# Yay_n_Ders_3.net
KiCad netlist of a schematic drawn in EAGLE
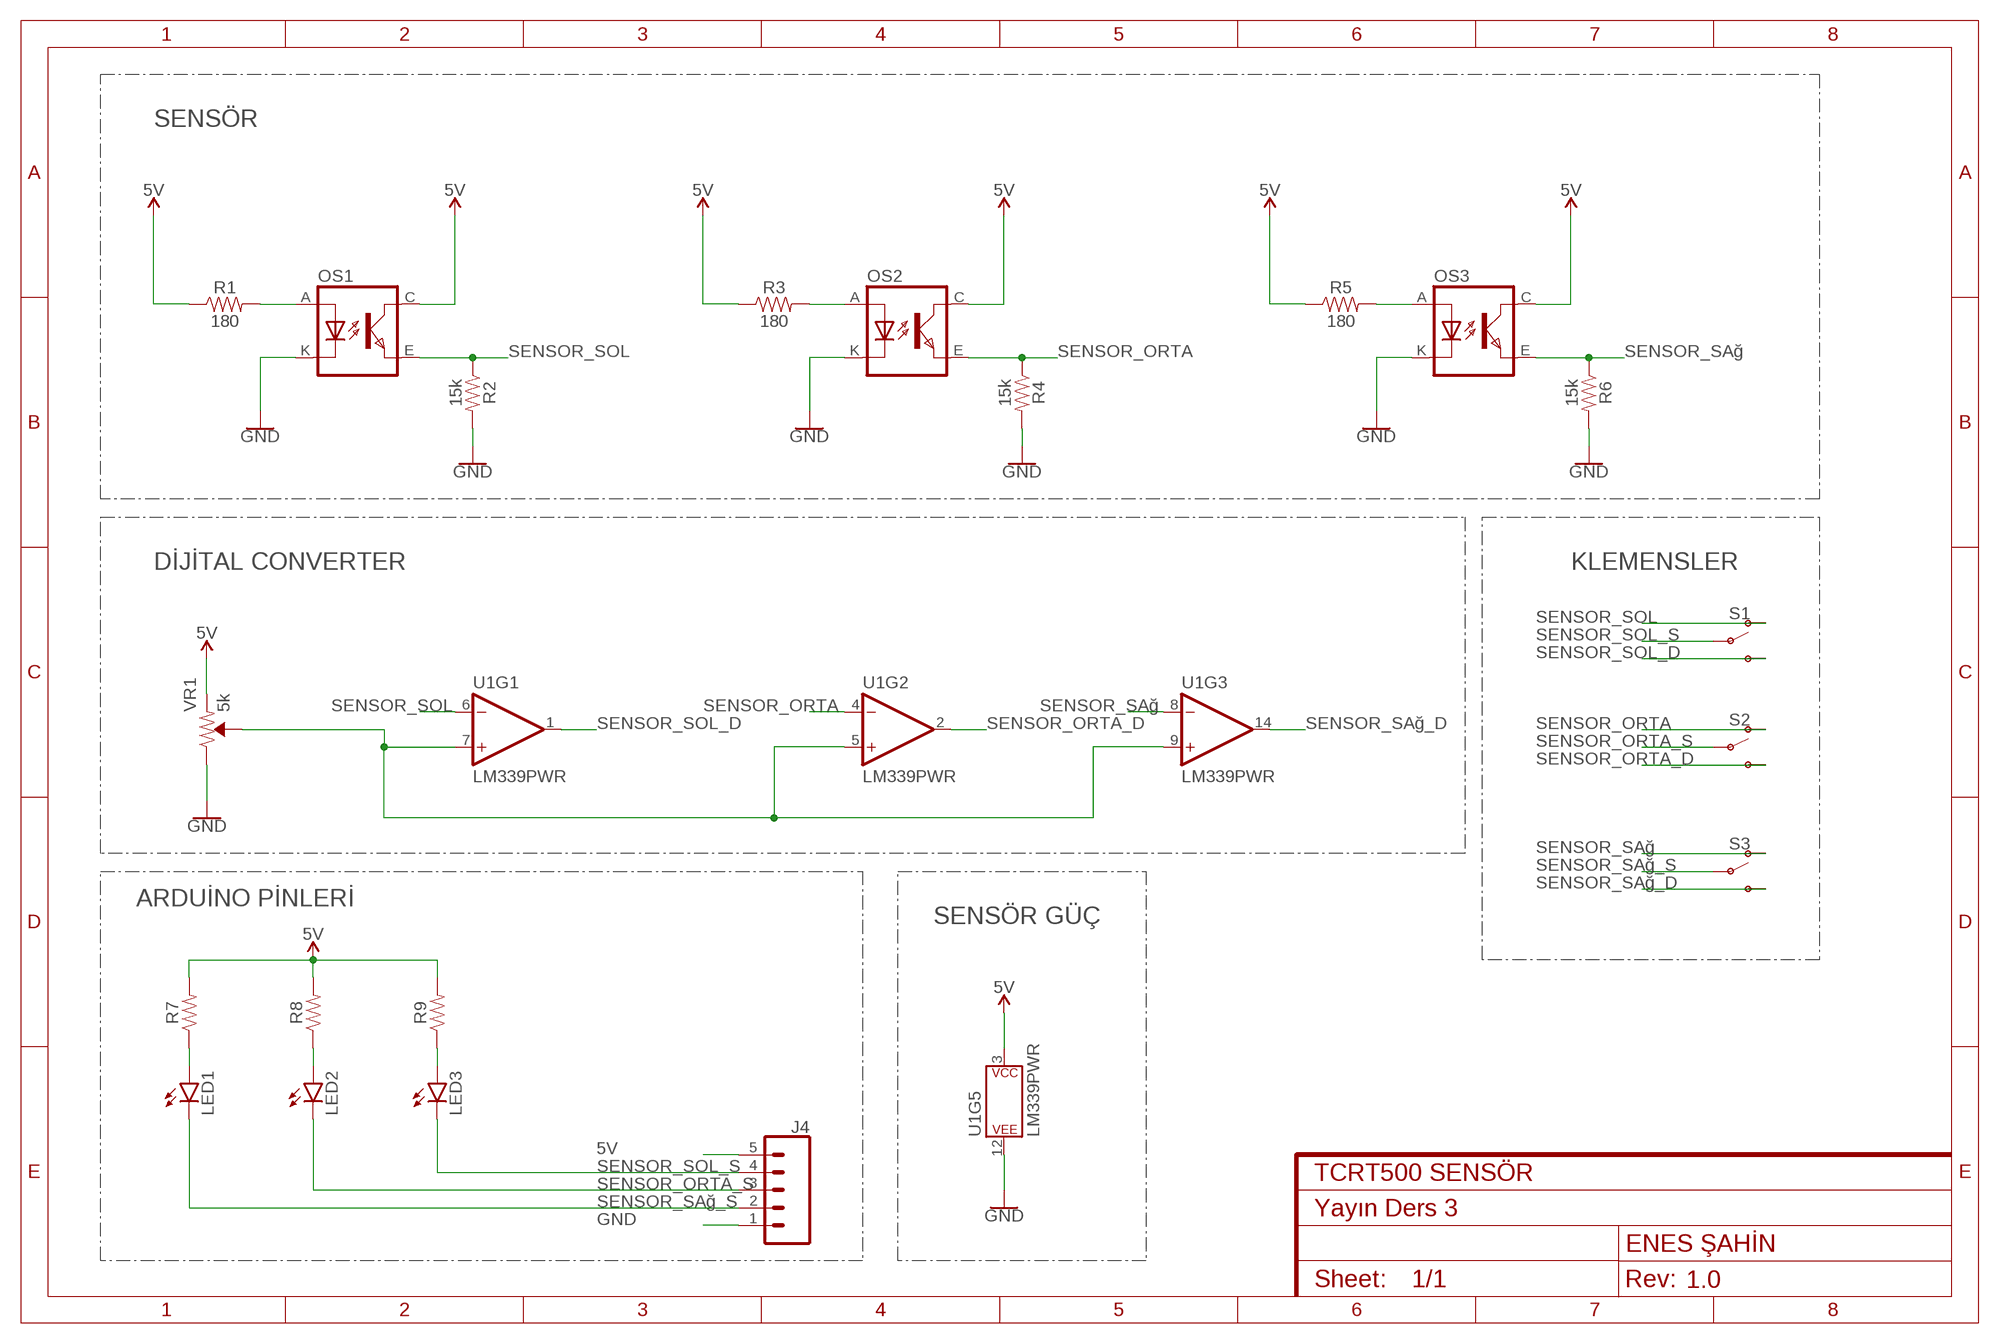
[diagram p0: schematic, sheet 1]

(export (version "E")
  (design (tool "Eeschema 10.0.6"))
  (components
    (comp (ref "J4")
      (value "CONN_05")
      (footprint "eagle-import:1X05")
      (libsource (lib "eagle-import") (part "CONN_05"))
    )
    (comp (ref "LED1")
      (value "LEDCHIP-LED0805")
      (footprint "eagle-import:CHIP-LED0805")
      (libsource (lib "eagle-import") (part "LEDCHIP-LED0805"))
    )
    (comp (ref "LED2")
      (value "LEDCHIP-LED0805")
      (footprint "eagle-import:CHIP-LED0805")
      (libsource (lib "eagle-import") (part "LEDCHIP-LED0805"))
    )
    (comp (ref "LED3")
      (value "LEDCHIP-LED0805")
      (footprint "eagle-import:CHIP-LED0805")
      (libsource (lib "eagle-import") (part "LEDCHIP-LED0805"))
    )
    (comp (ref "OS1")
      (value "TCRT5000")
      (footprint "eagle-import:TCRT5000")
      (libsource (lib "eagle-import") (part "TCRT5000"))
    )
    (comp (ref "OS2")
      (value "TCRT5000")
      (footprint "eagle-import:TCRT5000")
      (libsource (lib "eagle-import") (part "TCRT5000"))
    )
    (comp (ref "OS3")
      (value "TCRT5000")
      (footprint "eagle-import:TCRT5000")
      (libsource (lib "eagle-import") (part "TCRT5000"))
    )
    (comp (ref "R1")
      (value "180")
      (footprint "eagle-import:0805")
      (libsource (lib "eagle-import") (part "0.75OHM-0805-1/4W-1%"))
    )
    (comp (ref "R2")
      (value "15k")
      (footprint "eagle-import:0805")
      (libsource (lib "eagle-import") (part "0.75OHM-0805-1/4W-1%"))
    )
    (comp (ref "R3")
      (value "180")
      (footprint "eagle-import:0805")
      (libsource (lib "eagle-import") (part "0.75OHM-0805-1/4W-1%"))
    )
    (comp (ref "R4")
      (value "15k")
      (footprint "eagle-import:0805")
      (libsource (lib "eagle-import") (part "0.75OHM-0805-1/4W-1%"))
    )
    (comp (ref "R5")
      (value "180")
      (footprint "eagle-import:0805")
      (libsource (lib "eagle-import") (part "0.75OHM-0805-1/4W-1%"))
    )
    (comp (ref "R6")
      (value "15k")
      (footprint "eagle-import:0805")
      (libsource (lib "eagle-import") (part "0.75OHM-0805-1/4W-1%"))
    )
    (comp (ref "R7")
      (value "RESISTOR0805")
      (footprint "eagle-import:0805")
      (libsource (lib "eagle-import") (part "RESISTOR0805"))
    )
    (comp (ref "R8")
      (value "RESISTOR0805")
      (footprint "eagle-import:0805")
      (libsource (lib "eagle-import") (part "RESISTOR0805"))
    )
    (comp (ref "R9")
      (value "RESISTOR0805")
      (footprint "eagle-import:0805")
      (libsource (lib "eagle-import") (part "RESISTOR0805"))
    )
    (comp (ref "S1")
      (value "SWITCH-SPDT-SMD-RIGHT-ANGLE")
      (footprint "eagle-import:SWITCH_SPST_SMD_A")
      (libsource (lib "eagle-import") (part "SWITCH-SPDT-SMD-RIGHT-ANGLE"))
    )
    (comp (ref "S2")
      (value "SWITCH-SPDT-SMD-RIGHT-ANGLE")
      (footprint "eagle-import:SWITCH_SPST_SMD_A")
      (libsource (lib "eagle-import") (part "SWITCH-SPDT-SMD-RIGHT-ANGLE"))
    )
    (comp (ref "S3")
      (value "SWITCH-SPDT-SMD-RIGHT-ANGLE")
      (footprint "eagle-import:SWITCH_SPST_SMD_A")
      (libsource (lib "eagle-import") (part "SWITCH-SPDT-SMD-RIGHT-ANGLE"))
    )
    (comp (ref "U1")
      (value "LM339PWR")
      (footprint "eagle-import:TSSOP-14")
      (libsource (lib "eagle-import") (part "LM339"))
    )
    (comp (ref "VR1")
      (value "5k")
      (footprint "eagle-import:TRIMPOT-SMD-5MM")
      (libsource (lib "eagle-import") (part "TRIMPOT-SMD-5MM-CLOSED-1/4W-20%"))
    )
  )
  (nets
    (net (code "1") (name "/SENSOR_ORTA") (class "Default")
      (node (ref "OS2") (pin "E") (pinfunction "EMITTER_E") (pintype "passive"))
      (node (ref "R4") (pin "1") (pinfunction "1_1") (pintype "passive"))
      (node (ref "S2") (pin "1") (pinfunction "O_1") (pintype "passive"))
      (node (ref "U1") (pin "4") (pinfunction "-IN_4") (pintype "input"))
    )
    (net (code "2") (name "/SENSOR_ORTA_D") (class "Default")
      (node (ref "S2") (pin "3") (pinfunction "S_3") (pintype "passive"))
      (node (ref "U1") (pin "2") (pinfunction "OUT_2") (pintype "output"))
    )
    (net (code "3") (name "/SENSOR_ORTA_S") (class "Default")
      (node (ref "J4") (pin "3") (pinfunction "3_3") (pintype "passive"))
      (node (ref "LED2") (pin "C") (pinfunction "C_C") (pintype "passive"))
      (node (ref "S2") (pin "2") (pinfunction "P_2") (pintype "passive"))
    )
    (net (code "4") (name "/SENSOR_SAğ") (class "Default")
      (node (ref "OS3") (pin "E") (pinfunction "EMITTER_E") (pintype "passive"))
      (node (ref "R6") (pin "1") (pinfunction "1_1") (pintype "passive"))
      (node (ref "S3") (pin "1") (pinfunction "O_1") (pintype "passive"))
      (node (ref "U1") (pin "8") (pinfunction "-IN_8") (pintype "input"))
    )
    (net (code "5") (name "/SENSOR_SAğ_D") (class "Default")
      (node (ref "S3") (pin "3") (pinfunction "S_3") (pintype "passive"))
      (node (ref "U1") (pin "14") (pinfunction "OUT_14") (pintype "output"))
    )
    (net (code "6") (name "/SENSOR_SAğ_S") (class "Default")
      (node (ref "J4") (pin "2") (pinfunction "2_2") (pintype "passive"))
      (node (ref "LED1") (pin "C") (pinfunction "C_C") (pintype "passive"))
      (node (ref "S3") (pin "2") (pinfunction "P_2") (pintype "passive"))
    )
    (net (code "7") (name "/SENSOR_SOL") (class "Default")
      (node (ref "OS1") (pin "E") (pinfunction "EMITTER_E") (pintype "passive"))
      (node (ref "R2") (pin "1") (pinfunction "1_1") (pintype "passive"))
      (node (ref "S1") (pin "1") (pinfunction "O_1") (pintype "passive"))
      (node (ref "U1") (pin "6") (pinfunction "-IN_6") (pintype "input"))
    )
    (net (code "8") (name "/SENSOR_SOL_D") (class "Default")
      (node (ref "S1") (pin "3") (pinfunction "S_3") (pintype "passive"))
      (node (ref "U1") (pin "1") (pinfunction "OUT_1") (pintype "output"))
    )
    (net (code "9") (name "/SENSOR_SOL_S") (class "Default")
      (node (ref "J4") (pin "4") (pinfunction "4_4") (pintype "passive"))
      (node (ref "LED3") (pin "C") (pinfunction "C_C") (pintype "passive"))
      (node (ref "S1") (pin "2") (pinfunction "P_2") (pintype "passive"))
    )
    (net (code "10") (name "5V") (class "Default")
      (node (ref "J4") (pin "5") (pinfunction "5_5") (pintype "passive"))
      (node (ref "OS1") (pin "C") (pinfunction "COLLECTOR_C") (pintype "passive"))
      (node (ref "OS2") (pin "C") (pinfunction "COLLECTOR_C") (pintype "passive"))
      (node (ref "OS3") (pin "C") (pinfunction "COLLECTOR_C") (pintype "passive"))
      (node (ref "R1") (pin "1") (pinfunction "1_1") (pintype "passive"))
      (node (ref "R3") (pin "1") (pinfunction "1_1") (pintype "passive"))
      (node (ref "R5") (pin "1") (pinfunction "1_1") (pintype "passive"))
      (node (ref "R7") (pin "2") (pinfunction "2_2") (pintype "passive"))
      (node (ref "R8") (pin "2") (pinfunction "2_2") (pintype "passive"))
      (node (ref "R9") (pin "2") (pinfunction "2_2") (pintype "passive"))
      (node (ref "U1") (pin "3") (pinfunction "P$V+_3") (pintype "bidirectional"))
      (node (ref "VR1") (pin "A") (pinfunction "CCW_A") (pintype "passive"))
    )
    (net (code "11") (name "GND") (class "Default")
      (node (ref "J4") (pin "1") (pinfunction "1_1") (pintype "passive"))
      (node (ref "OS1") (pin "K") (pinfunction "CATHODE_K") (pintype "passive"))
      (node (ref "OS2") (pin "K") (pinfunction "CATHODE_K") (pintype "passive"))
      (node (ref "OS3") (pin "K") (pinfunction "CATHODE_K") (pintype "passive"))
      (node (ref "R2") (pin "2") (pinfunction "2_2") (pintype "passive"))
      (node (ref "R4") (pin "2") (pinfunction "2_2") (pintype "passive"))
      (node (ref "R6") (pin "2") (pinfunction "2_2") (pintype "passive"))
      (node (ref "U1") (pin "12") (pinfunction "P$V-_12") (pintype "bidirectional"))
      (node (ref "VR1") (pin "C") (pinfunction "CW_C") (pintype "passive"))
    )
    (net (code "12") (name "Net-(LED1-PadA)") (class "Default")
      (node (ref "LED1") (pin "A") (pinfunction "A_A") (pintype "passive"))
      (node (ref "R7") (pin "1") (pinfunction "1_1") (pintype "passive"))
    )
    (net (code "13") (name "Net-(LED2-PadA)") (class "Default")
      (node (ref "LED2") (pin "A") (pinfunction "A_A") (pintype "passive"))
      (node (ref "R8") (pin "1") (pinfunction "1_1") (pintype "passive"))
    )
    (net (code "14") (name "Net-(LED3-PadA)") (class "Default")
      (node (ref "LED3") (pin "A") (pinfunction "A_A") (pintype "passive"))
      (node (ref "R9") (pin "1") (pinfunction "1_1") (pintype "passive"))
    )
    (net (code "15") (name "Net-(OS1-ANODE)") (class "Default")
      (node (ref "OS1") (pin "A") (pinfunction "ANODE_A") (pintype "passive"))
      (node (ref "R1") (pin "2") (pinfunction "2_2") (pintype "passive"))
    )
    (net (code "16") (name "Net-(OS2-ANODE)") (class "Default")
      (node (ref "OS2") (pin "A") (pinfunction "ANODE_A") (pintype "passive"))
      (node (ref "R3") (pin "2") (pinfunction "2_2") (pintype "passive"))
    )
    (net (code "17") (name "Net-(OS3-ANODE)") (class "Default")
      (node (ref "OS3") (pin "A") (pinfunction "ANODE_A") (pintype "passive"))
      (node (ref "R5") (pin "2") (pinfunction "2_2") (pintype "passive"))
    )
    (net (code "18") (name "Net-(U1A-+IN)") (class "Default")
      (node (ref "U1") (pin "5") (pinfunction "+IN_5") (pintype "input"))
      (node (ref "U1") (pin "7") (pinfunction "+IN_7") (pintype "input"))
      (node (ref "U1") (pin "9") (pinfunction "+IN_9") (pintype "input"))
      (node (ref "VR1") (pin "B") (pinfunction "WIPER_B") (pintype "passive"))
    )
  )
)
